# BatMeas5_1.net
KiCad netlist of a schematic drawn in EAGLE
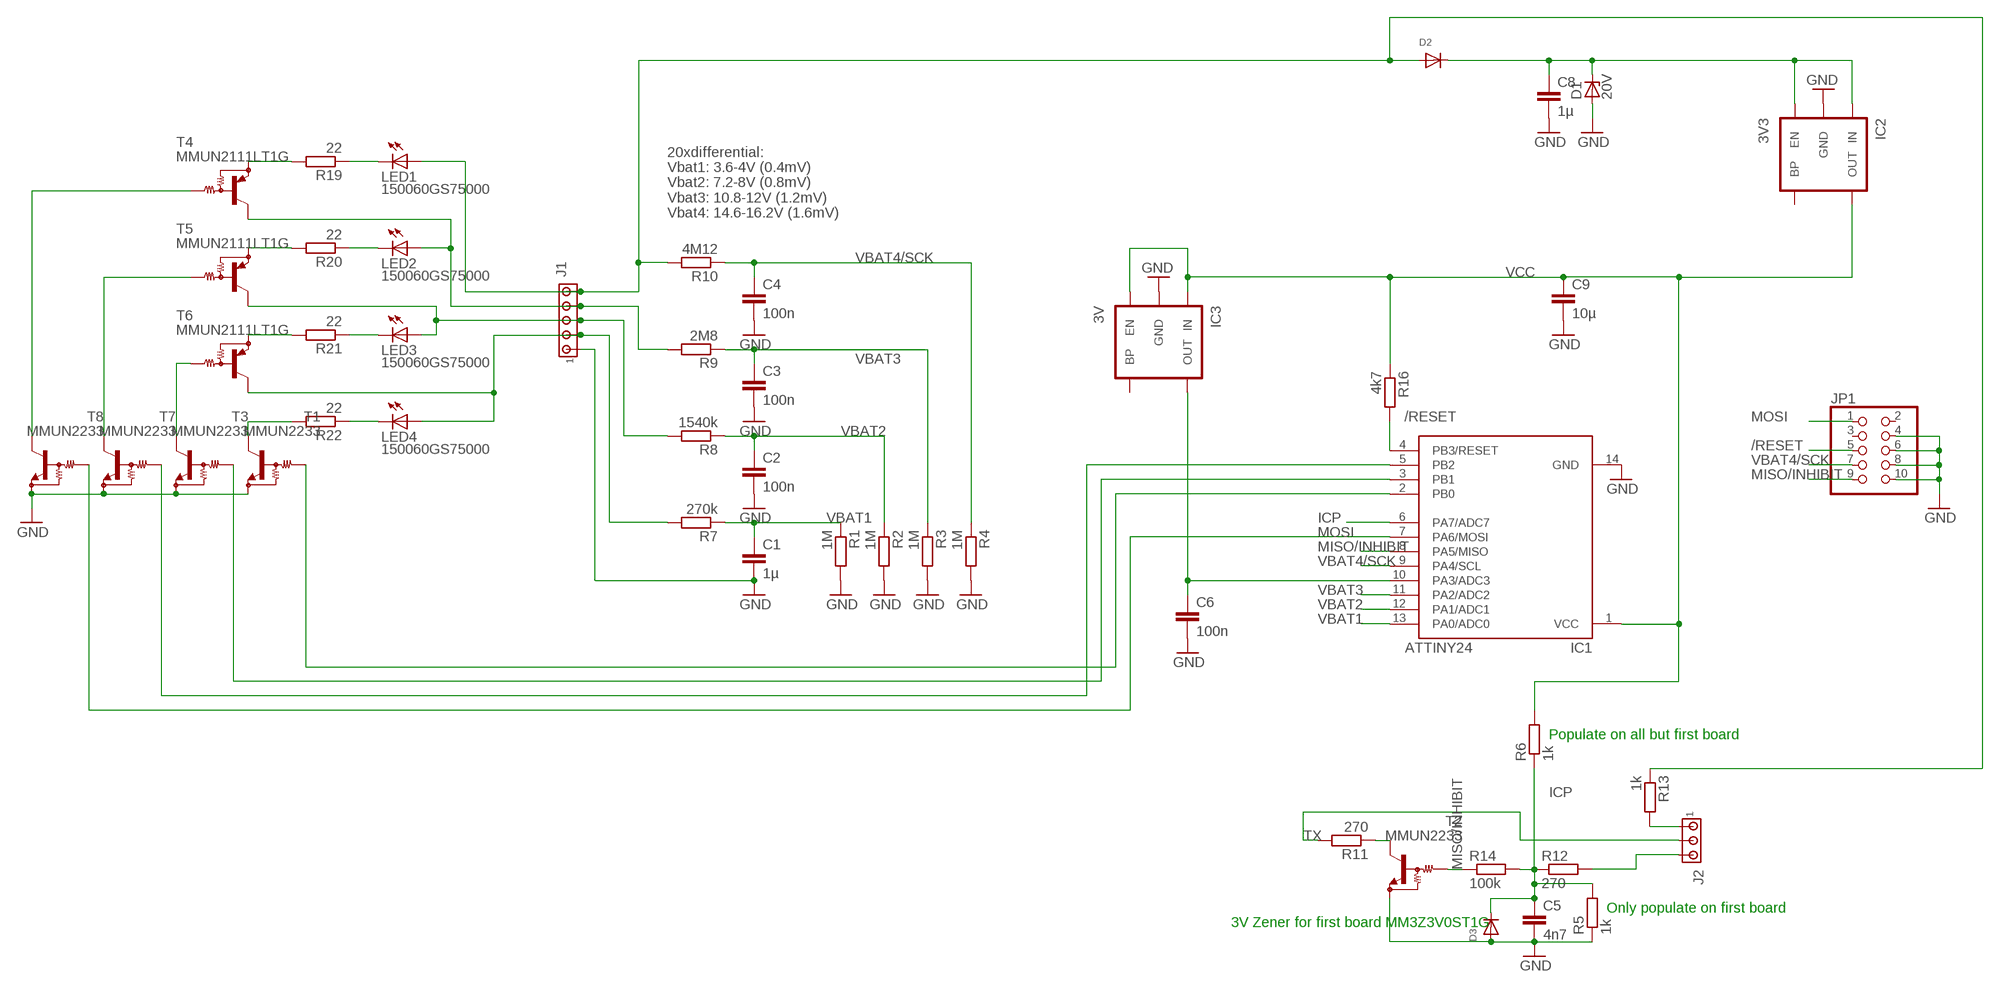
[diagram p0: schematic, sheet 1]

(export (version "E")
  (design (tool "Eeschema 10.0.6"))
  (components
    (comp (ref "C1")
      (value "1µ")
      (footprint "eagle-import:C0603")
      (libsource (lib "eagle-import") (part "C-EUC0603"))
    )
    (comp (ref "C2")
      (value "100n")
      (footprint "eagle-import:C0603")
      (libsource (lib "eagle-import") (part "C-EUC0603"))
    )
    (comp (ref "C3")
      (value "100n")
      (footprint "eagle-import:C0603")
      (libsource (lib "eagle-import") (part "C-EUC0603"))
    )
    (comp (ref "C4")
      (value "100n")
      (footprint "eagle-import:C0603")
      (libsource (lib "eagle-import") (part "C-EUC0603"))
    )
    (comp (ref "C5")
      (value "4n7")
      (footprint "eagle-import:C0603")
      (libsource (lib "eagle-import") (part "C-EUC0603"))
    )
    (comp (ref "C6")
      (value "100n")
      (footprint "eagle-import:C0603")
      (libsource (lib "eagle-import") (part "C-EUC0603"))
    )
    (comp (ref "C8")
      (value "1µ")
      (footprint "eagle-import:C0805")
      (libsource (lib "eagle-import") (part "C-EUC0805"))
    )
    (comp (ref "C9")
      (value "10µ")
      (footprint "eagle-import:C0805")
      (libsource (lib "eagle-import") (part "C-EUC0805"))
    )
    (comp (ref "D1")
      (value "20V")
      (footprint "eagle-import:SMB")
      (libsource (lib "eagle-import") (part "ZENER-DIODESMB"))
    )
    (comp (ref "D2")
      (value "DIODESOD-323F")
      (footprint "eagle-import:SOD-323F")
      (libsource (lib "eagle-import") (part "DIODESOD-323F"))
    )
    (comp (ref "D3")
      (value "DIODESOD-323F")
      (footprint "eagle-import:SOD-323F")
      (libsource (lib "eagle-import") (part "DIODESOD-323F"))
    )
    (comp (ref "IC1")
      (value "ATTINY24")
      (footprint "eagle-import:SO014")
      (libsource (lib "eagle-import") (part "ATTINY24"))
    )
    (comp (ref "IC2")
      (value "3V3")
      (footprint "eagle-import:SOT23-5")
      (libsource (lib "eagle-import") (part "V_REG_LDOSMD"))
    )
    (comp (ref "IC3")
      (value "3V")
      (footprint "eagle-import:SOT23-5")
      (libsource (lib "eagle-import") (part "V_REG_LDOSMD"))
    )
    (comp (ref "J1")
      (value "MTA05-100")
      (footprint "eagle-import:10X05MTA")
      (libsource (lib "eagle-import") (part "MTA05-100"))
    )
    (comp (ref "J2")
      (value "MTA03-100")
      (footprint "eagle-import:10X03MTA")
      (libsource (lib "eagle-import") (part "MTA03-100"))
    )
    (comp (ref "JP1")
      (value "PINHD-2X5")
      (footprint "eagle-import:2X05")
      (libsource (lib "eagle-import") (part "PINHD-2X5"))
    )
    (comp (ref "LED1")
      (value "150060GS75000")
      (footprint "eagle-import:CHIPLED_0805")
      (libsource (lib "eagle-import") (part "LEDCHIPLED_0805"))
    )
    (comp (ref "LED2")
      (value "150060GS75000")
      (footprint "eagle-import:CHIPLED_0805")
      (libsource (lib "eagle-import") (part "LEDCHIPLED_0805"))
    )
    (comp (ref "LED3")
      (value "150060GS75000")
      (footprint "eagle-import:CHIPLED_0805")
      (libsource (lib "eagle-import") (part "LEDCHIPLED_0805"))
    )
    (comp (ref "LED4")
      (value "150060GS75000")
      (footprint "eagle-import:CHIPLED_0805")
      (libsource (lib "eagle-import") (part "LEDCHIPLED_0805"))
    )
    (comp (ref "R1")
      (value "1M")
      (footprint "eagle-import:R0603")
      (libsource (lib "eagle-import") (part "R-EU_R0603"))
    )
    (comp (ref "R2")
      (value "1M")
      (footprint "eagle-import:R0603")
      (libsource (lib "eagle-import") (part "R-EU_R0603"))
    )
    (comp (ref "R3")
      (value "1M")
      (footprint "eagle-import:R0603")
      (libsource (lib "eagle-import") (part "R-EU_R0603"))
    )
    (comp (ref "R4")
      (value "1M")
      (footprint "eagle-import:R0603")
      (libsource (lib "eagle-import") (part "R-EU_R0603"))
    )
    (comp (ref "R5")
      (value "1k")
      (footprint "eagle-import:R0603")
      (libsource (lib "eagle-import") (part "R-EU_R0603"))
    )
    (comp (ref "R6")
      (value "1k")
      (footprint "eagle-import:R0603")
      (libsource (lib "eagle-import") (part "R-EU_R0603"))
    )
    (comp (ref "R7")
      (value "270k")
      (footprint "eagle-import:R0603")
      (libsource (lib "eagle-import") (part "R-EU_R0603"))
    )
    (comp (ref "R8")
      (value "1540k")
      (footprint "eagle-import:R0603")
      (libsource (lib "eagle-import") (part "R-EU_R0603"))
    )
    (comp (ref "R9")
      (value "2M8")
      (footprint "eagle-import:R0603")
      (libsource (lib "eagle-import") (part "R-EU_R0603"))
    )
    (comp (ref "R10")
      (value "4M12")
      (footprint "eagle-import:R0603")
      (libsource (lib "eagle-import") (part "R-EU_R0603"))
    )
    (comp (ref "R11")
      (value "270")
      (footprint "eagle-import:R0603")
      (libsource (lib "eagle-import") (part "R-EU_R0603"))
    )
    (comp (ref "R12")
      (value "270")
      (footprint "eagle-import:R0603")
      (libsource (lib "eagle-import") (part "R-EU_R0603"))
    )
    (comp (ref "R13")
      (value "1k")
      (footprint "eagle-import:R0603")
      (libsource (lib "eagle-import") (part "R-EU_R0603"))
    )
    (comp (ref "R14")
      (value "100k")
      (footprint "eagle-import:R0603")
      (libsource (lib "eagle-import") (part "R-EU_R0603"))
    )
    (comp (ref "R16")
      (value "4k7")
      (footprint "eagle-import:R0603")
      (libsource (lib "eagle-import") (part "R-EU_R0603"))
    )
    (comp (ref "R19")
      (value "22")
      (footprint "eagle-import:R0805")
      (libsource (lib "eagle-import") (part "R-EU_R0805"))
    )
    (comp (ref "R20")
      (value "22")
      (footprint "eagle-import:R0805")
      (libsource (lib "eagle-import") (part "R-EU_R0805"))
    )
    (comp (ref "R21")
      (value "22")
      (footprint "eagle-import:R0805")
      (libsource (lib "eagle-import") (part "R-EU_R0805"))
    )
    (comp (ref "R22")
      (value "22")
      (footprint "eagle-import:R0805")
      (libsource (lib "eagle-import") (part "R-EU_R0805"))
    )
    (comp (ref "T1")
      (value "MMUN2233")
      (footprint "eagle-import:SC59-BEC")
      (libsource (lib "eagle-import") (part "-NPN_DRIVER-SC59-BECMUN2211T1"))
    )
    (comp (ref "T2")
      (value "MMUN2233")
      (footprint "eagle-import:SC59-BEC")
      (libsource (lib "eagle-import") (part "-NPN_DRIVER-SC59-BECMUN2211T1"))
    )
    (comp (ref "T3")
      (value "MMUN2233")
      (footprint "eagle-import:SC59-BEC")
      (libsource (lib "eagle-import") (part "-NPN_DRIVER-SC59-BECMUN2211T1"))
    )
    (comp (ref "T4")
      (value "MMUN2111LT1G")
      (footprint "eagle-import:SC59-BEC")
      (libsource (lib "eagle-import") (part "-PNP_DRIVER-SC59-BECMUN2111T1"))
    )
    (comp (ref "T5")
      (value "MMUN2111LT1G")
      (footprint "eagle-import:SC59-BEC")
      (libsource (lib "eagle-import") (part "-PNP_DRIVER-SC59-BECMUN2111T1"))
    )
    (comp (ref "T6")
      (value "MMUN2111LT1G")
      (footprint "eagle-import:SC59-BEC")
      (libsource (lib "eagle-import") (part "-PNP_DRIVER-SC59-BECMUN2111T1"))
    )
    (comp (ref "T7")
      (value "MMUN2233")
      (footprint "eagle-import:SC59-BEC")
      (libsource (lib "eagle-import") (part "-NPN_DRIVER-SC59-BECMUN2211T1"))
    )
    (comp (ref "T8")
      (value "MMUN2233")
      (footprint "eagle-import:SC59-BEC")
      (libsource (lib "eagle-import") (part "-NPN_DRIVER-SC59-BECMUN2211T1"))
    )
  )
  (nets
    (net (code "1") (name "/ICP") (class "Default")
      (node (ref "C5") (pin "1") (pinfunction "1_1") (pintype "passive"))
      (node (ref "D3") (pin "C") (pinfunction "C_C") (pintype "passive"))
      (node (ref "IC1") (pin "6") (pinfunction "PA7/ADC7_6") (pintype "bidirectional"))
      (node (ref "R12") (pin "1") (pinfunction "1_1") (pintype "passive"))
      (node (ref "R14") (pin "2") (pinfunction "2_2") (pintype "passive"))
      (node (ref "R5") (pin "2") (pinfunction "2_2") (pintype "passive"))
      (node (ref "R6") (pin "1") (pinfunction "1_1") (pintype "passive"))
    )
    (net (code "2") (name "/MISO{slash}INHIBIT") (class "Default")
      (node (ref "IC1") (pin "8") (pinfunction "PA5/MISO_8") (pintype "bidirectional"))
      (node (ref "JP1") (pin "9") (pinfunction "9_9") (pintype "passive"))
      (node (ref "R14") (pin "1") (pinfunction "1_1") (pintype "passive"))
      (node (ref "T2") (pin "B") (pinfunction "B_B") (pintype "passive"))
    )
    (net (code "3") (name "/MOSI") (class "Default")
      (node (ref "IC1") (pin "7") (pinfunction "PA6/MOSI_7") (pintype "bidirectional"))
      (node (ref "JP1") (pin "1") (pinfunction "1_1") (pintype "passive"))
      (node (ref "T8") (pin "B") (pinfunction "B_B") (pintype "passive"))
    )
    (net (code "4") (name "/TX") (class "Default")
      (node (ref "J2") (pin "2") (pinfunction "2_2") (pintype "passive"))
      (node (ref "R11") (pin "2") (pinfunction "2_2") (pintype "passive"))
    )
    (net (code "5") (name "/VBAT1") (class "Default")
      (node (ref "C1") (pin "1") (pinfunction "1_1") (pintype "passive"))
      (node (ref "IC1") (pin "13") (pinfunction "PA0/ADC0_13") (pintype "bidirectional"))
      (node (ref "R1") (pin "1") (pinfunction "1_1") (pintype "passive"))
      (node (ref "R7") (pin "1") (pinfunction "1_1") (pintype "passive"))
    )
    (net (code "6") (name "/VBAT2") (class "Default")
      (node (ref "C2") (pin "1") (pinfunction "1_1") (pintype "passive"))
      (node (ref "IC1") (pin "12") (pinfunction "PA1/ADC1_12") (pintype "bidirectional"))
      (node (ref "R2") (pin "1") (pinfunction "1_1") (pintype "passive"))
      (node (ref "R8") (pin "1") (pinfunction "1_1") (pintype "passive"))
    )
    (net (code "7") (name "/VBAT3") (class "Default")
      (node (ref "C3") (pin "1") (pinfunction "1_1") (pintype "passive"))
      (node (ref "IC1") (pin "11") (pinfunction "PA2/ADC2_11") (pintype "bidirectional"))
      (node (ref "R3") (pin "1") (pinfunction "1_1") (pintype "passive"))
      (node (ref "R9") (pin "1") (pinfunction "1_1") (pintype "passive"))
    )
    (net (code "8") (name "/VBAT4{slash}SCK") (class "Default")
      (node (ref "C4") (pin "1") (pinfunction "1_1") (pintype "passive"))
      (node (ref "IC1") (pin "9") (pinfunction "PA4/SCL_9") (pintype "bidirectional"))
      (node (ref "JP1") (pin "7") (pinfunction "7_7") (pintype "passive"))
      (node (ref "R10") (pin "1") (pinfunction "1_1") (pintype "passive"))
      (node (ref "R4") (pin "1") (pinfunction "1_1") (pintype "passive"))
    )
    (net (code "9") (name "/VCC") (class "Default")
      (node (ref "C9") (pin "1") (pinfunction "1_1") (pintype "passive"))
      (node (ref "IC1") (pin "1") (pinfunction "VCC_1") (pintype "bidirectional"))
      (node (ref "IC2") (pin "5") (pinfunction "OUT_5") (pintype "passive"))
      (node (ref "IC3") (pin "1") (pinfunction "IN_1") (pintype "input"))
      (node (ref "IC3") (pin "3") (pinfunction "EN_3") (pintype "input"))
      (node (ref "R16") (pin "1") (pinfunction "1_1") (pintype "passive"))
      (node (ref "R6") (pin "2") (pinfunction "2_2") (pintype "passive"))
    )
    (net (code "10") (name "/{slash}RESET") (class "Default")
      (node (ref "IC1") (pin "4") (pinfunction "PB3/RESET_4") (pintype "bidirectional"))
      (node (ref "JP1") (pin "5") (pinfunction "5_5") (pintype "passive"))
      (node (ref "R16") (pin "2") (pinfunction "2_2") (pintype "passive"))
    )
    (net (code "11") (name "GND") (class "Default")
      (node (ref "C1") (pin "2") (pinfunction "2_2") (pintype "passive"))
      (node (ref "C2") (pin "2") (pinfunction "2_2") (pintype "passive"))
      (node (ref "C3") (pin "2") (pinfunction "2_2") (pintype "passive"))
      (node (ref "C4") (pin "2") (pinfunction "2_2") (pintype "passive"))
      (node (ref "C5") (pin "2") (pinfunction "2_2") (pintype "passive"))
      (node (ref "C6") (pin "2") (pinfunction "2_2") (pintype "passive"))
      (node (ref "C8") (pin "2") (pinfunction "2_2") (pintype "passive"))
      (node (ref "C9") (pin "2") (pinfunction "2_2") (pintype "passive"))
      (node (ref "D1") (pin "A") (pinfunction "A_A") (pintype "passive"))
      (node (ref "D3") (pin "A") (pinfunction "A_A") (pintype "passive"))
      (node (ref "IC1") (pin "14") (pinfunction "GND_14") (pintype "bidirectional"))
      (node (ref "IC2") (pin "2") (pinfunction "GND_2") (pintype "input"))
      (node (ref "IC3") (pin "2") (pinfunction "GND_2") (pintype "input"))
      (node (ref "J1") (pin "1") (pinfunction "1_1") (pintype "passive"))
      (node (ref "JP1") (pin "10") (pinfunction "10_10") (pintype "passive"))
      (node (ref "JP1") (pin "4") (pinfunction "4_4") (pintype "passive"))
      (node (ref "JP1") (pin "6") (pinfunction "6_6") (pintype "passive"))
      (node (ref "JP1") (pin "8") (pinfunction "8_8") (pintype "passive"))
      (node (ref "R1") (pin "2") (pinfunction "2_2") (pintype "passive"))
      (node (ref "R2") (pin "2") (pinfunction "2_2") (pintype "passive"))
      (node (ref "R3") (pin "2") (pinfunction "2_2") (pintype "passive"))
      (node (ref "R4") (pin "2") (pinfunction "2_2") (pintype "passive"))
      (node (ref "R5") (pin "1") (pinfunction "1_1") (pintype "passive"))
      (node (ref "T1") (pin "E") (pinfunction "E_E") (pintype "passive"))
      (node (ref "T2") (pin "E") (pinfunction "E_E") (pintype "passive"))
      (node (ref "T3") (pin "E") (pinfunction "E_E") (pintype "passive"))
      (node (ref "T7") (pin "E") (pinfunction "E_E") (pintype "passive"))
      (node (ref "T8") (pin "E") (pinfunction "E_E") (pintype "passive"))
    )
    (net (code "12") (name "Net-(D2-PadA)") (class "Default")
      (node (ref "D2") (pin "A") (pinfunction "A_A") (pintype "passive"))
      (node (ref "J1") (pin "5") (pinfunction "5_5") (pintype "passive"))
      (node (ref "LED1") (pin "A") (pinfunction "A_A") (pintype "passive"))
      (node (ref "R10") (pin "2") (pinfunction "2_2") (pintype "passive"))
      (node (ref "R13") (pin "1") (pinfunction "1_1") (pintype "passive"))
    )
    (net (code "13") (name "Net-(IC1-PA3{slash}ADC3)") (class "Default")
      (node (ref "C6") (pin "1") (pinfunction "1_1") (pintype "passive"))
      (node (ref "IC1") (pin "10") (pinfunction "PA3/ADC3_10") (pintype "bidirectional"))
      (node (ref "IC3") (pin "5") (pinfunction "OUT_5") (pintype "passive"))
    )
    (net (code "14") (name "Net-(IC1-PB0)") (class "Default")
      (node (ref "IC1") (pin "2") (pinfunction "PB0_2") (pintype "bidirectional"))
      (node (ref "T1") (pin "B") (pinfunction "B_B") (pintype "passive"))
    )
    (net (code "15") (name "Net-(IC1-PB1)") (class "Default")
      (node (ref "IC1") (pin "3") (pinfunction "PB1_3") (pintype "bidirectional"))
      (node (ref "T3") (pin "B") (pinfunction "B_B") (pintype "passive"))
    )
    (net (code "16") (name "Net-(IC1-PB2)") (class "Default")
      (node (ref "IC1") (pin "5") (pinfunction "PB2_5") (pintype "bidirectional"))
      (node (ref "T7") (pin "B") (pinfunction "B_B") (pintype "passive"))
    )
    (net (code "17") (name "Net-(IC2-EN)") (class "Default")
      (node (ref "C8") (pin "1") (pinfunction "1_1") (pintype "passive"))
      (node (ref "D1") (pin "C") (pinfunction "C_C") (pintype "passive"))
      (node (ref "D2") (pin "C") (pinfunction "C_C") (pintype "passive"))
      (node (ref "IC2") (pin "1") (pinfunction "IN_1") (pintype "input"))
      (node (ref "IC2") (pin "3") (pinfunction "EN_3") (pintype "input"))
    )
    (net (code "18") (name "Net-(J1-Pad2)") (class "Default")
      (node (ref "J1") (pin "2") (pinfunction "2_2") (pintype "passive"))
      (node (ref "LED4") (pin "A") (pinfunction "A_A") (pintype "passive"))
      (node (ref "R7") (pin "2") (pinfunction "2_2") (pintype "passive"))
      (node (ref "T6") (pin "C") (pinfunction "C_C") (pintype "passive"))
    )
    (net (code "19") (name "Net-(J1-Pad3)") (class "Default")
      (node (ref "J1") (pin "3") (pinfunction "3_3") (pintype "passive"))
      (node (ref "LED3") (pin "A") (pinfunction "A_A") (pintype "passive"))
      (node (ref "R8") (pin "2") (pinfunction "2_2") (pintype "passive"))
      (node (ref "T5") (pin "C") (pinfunction "C_C") (pintype "passive"))
    )
    (net (code "20") (name "Net-(J1-Pad4)") (class "Default")
      (node (ref "J1") (pin "4") (pinfunction "4_4") (pintype "passive"))
      (node (ref "LED2") (pin "A") (pinfunction "A_A") (pintype "passive"))
      (node (ref "R9") (pin "2") (pinfunction "2_2") (pintype "passive"))
      (node (ref "T4") (pin "C") (pinfunction "C_C") (pintype "passive"))
    )
    (net (code "21") (name "Net-(J2-Pad1)") (class "Default")
      (node (ref "J2") (pin "1") (pinfunction "1_1") (pintype "passive"))
      (node (ref "R13") (pin "2") (pinfunction "2_2") (pintype "passive"))
    )
    (net (code "22") (name "Net-(J2-Pad3)") (class "Default")
      (node (ref "J2") (pin "3") (pinfunction "3_3") (pintype "passive"))
      (node (ref "R12") (pin "2") (pinfunction "2_2") (pintype "passive"))
    )
    (net (code "23") (name "Net-(LED1-PadC)") (class "Default")
      (node (ref "LED1") (pin "C") (pinfunction "C_C") (pintype "passive"))
      (node (ref "R19") (pin "1") (pinfunction "1_1") (pintype "passive"))
    )
    (net (code "24") (name "Net-(LED2-PadC)") (class "Default")
      (node (ref "LED2") (pin "C") (pinfunction "C_C") (pintype "passive"))
      (node (ref "R20") (pin "1") (pinfunction "1_1") (pintype "passive"))
    )
    (net (code "25") (name "Net-(LED3-PadC)") (class "Default")
      (node (ref "LED3") (pin "C") (pinfunction "C_C") (pintype "passive"))
      (node (ref "R21") (pin "1") (pinfunction "1_1") (pintype "passive"))
    )
    (net (code "26") (name "Net-(LED4-PadC)") (class "Default")
      (node (ref "LED4") (pin "C") (pinfunction "C_C") (pintype "passive"))
      (node (ref "R22") (pin "1") (pinfunction "1_1") (pintype "passive"))
    )
    (net (code "27") (name "Net-(R11-Pad1)") (class "Default")
      (node (ref "R11") (pin "1") (pinfunction "1_1") (pintype "passive"))
      (node (ref "T2") (pin "C") (pinfunction "C_C") (pintype "passive"))
    )
    (net (code "28") (name "Net-(R19-Pad2)") (class "Default")
      (node (ref "R19") (pin "2") (pinfunction "2_2") (pintype "passive"))
      (node (ref "T4") (pin "E") (pinfunction "E_E") (pintype "passive"))
    )
    (net (code "29") (name "Net-(R20-Pad2)") (class "Default")
      (node (ref "R20") (pin "2") (pinfunction "2_2") (pintype "passive"))
      (node (ref "T5") (pin "E") (pinfunction "E_E") (pintype "passive"))
    )
    (net (code "30") (name "Net-(R21-Pad2)") (class "Default")
      (node (ref "R21") (pin "2") (pinfunction "2_2") (pintype "passive"))
      (node (ref "T6") (pin "E") (pinfunction "E_E") (pintype "passive"))
    )
    (net (code "31") (name "Net-(R22-Pad2)") (class "Default")
      (node (ref "R22") (pin "2") (pinfunction "2_2") (pintype "passive"))
      (node (ref "T1") (pin "C") (pinfunction "C_C") (pintype "passive"))
    )
    (net (code "32") (name "Net-(T3-PadC)") (class "Default")
      (node (ref "T3") (pin "C") (pinfunction "C_C") (pintype "passive"))
      (node (ref "T6") (pin "B") (pinfunction "B_B") (pintype "passive"))
    )
    (net (code "33") (name "Net-(T4-PadB)") (class "Default")
      (node (ref "T4") (pin "B") (pinfunction "B_B") (pintype "passive"))
      (node (ref "T8") (pin "C") (pinfunction "C_C") (pintype "passive"))
    )
    (net (code "34") (name "Net-(T5-PadB)") (class "Default")
      (node (ref "T5") (pin "B") (pinfunction "B_B") (pintype "passive"))
      (node (ref "T7") (pin "C") (pinfunction "C_C") (pintype "passive"))
    )
    (net (code "35") (name "unconnected-(IC2-BP-Pad4)") (class "Default")
      (node (ref "IC2") (pin "4") (pinfunction "BP_4") (pintype "input"))
    )
    (net (code "36") (name "unconnected-(IC3-BP-Pad4)") (class "Default")
      (node (ref "IC3") (pin "4") (pinfunction "BP_4") (pintype "input"))
    )
    (net (code "37") (name "unconnected-(JP1-Pad2)") (class "Default")
      (node (ref "JP1") (pin "2") (pinfunction "2_2") (pintype "passive"))
    )
    (net (code "38") (name "unconnected-(JP1-Pad3)") (class "Default")
      (node (ref "JP1") (pin "3") (pinfunction "3_3") (pintype "passive"))
    )
  )
)
